# 5_EEPROM.net
KiCad netlist of a schematic drawn in Altium Designer
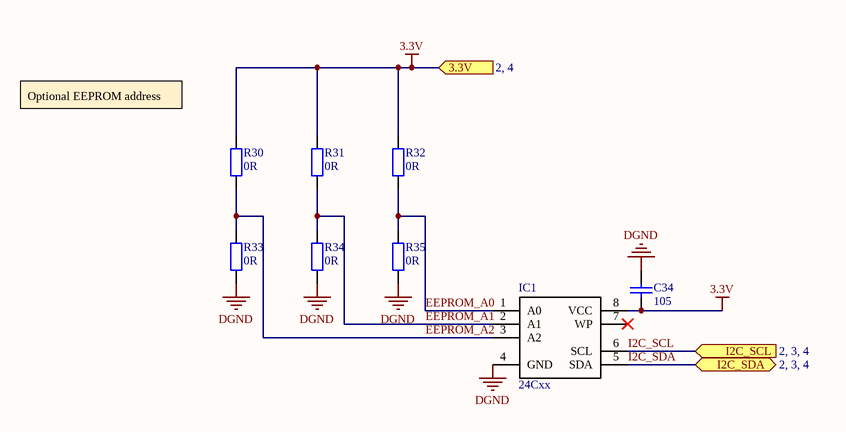
[diagram p0: [5]EEPROM.SchDoc]

(export (version "E")
  (design (tool "Eeschema 10.0.6"))
  (components
    (comp (ref "C34")
      (value "105")
      (footprint "tu 0805")
      (description "Dán")
      (libsource (lib "Tu dien") (part "Tu 0805 105 50V 10%"))
    )
    (comp (ref "IC1")
      (value "24Cxx")
      (footprint "SO8")
      (description "Standard 2-Wire Bus Interface Serial EEPROM")
      (fields (field (name "COPYRIGHT BY") "VanDungEvn"))
      (libsource (lib "LIBRARY") (part "24Cxx"))
    )
    (comp (ref "R30")
      (value "0R")
      (footprint "tro smd 0805")
      (description "Dán")
      (libsource (lib "Dien Tro") (part "Tro 0805 5% 0R"))
    )
    (comp (ref "R31")
      (value "0R")
      (footprint "tro smd 0805")
      (description "Dán")
      (libsource (lib "Dien Tro") (part "Tro 0805 5% 0R"))
    )
    (comp (ref "R32")
      (value "0R")
      (footprint "tro smd 0805")
      (description "Dán")
      (libsource (lib "Dien Tro") (part "Tro 0805 5% 0R"))
    )
    (comp (ref "R33")
      (value "0R")
      (footprint "tro smd 0805")
      (description "Dán")
      (libsource (lib "Dien Tro") (part "Tro 0805 5% 0R"))
    )
    (comp (ref "R34")
      (value "0R")
      (footprint "tro smd 0805")
      (description "Dán")
      (libsource (lib "Dien Tro") (part "Tro 0805 5% 0R"))
    )
    (comp (ref "R35")
      (value "0R")
      (footprint "tro smd 0805")
      (description "Dán")
      (libsource (lib "Dien Tro") (part "Tro 0805 5% 0R"))
    )
  )
  (nets
    (net (code "1") (name "/EEPROM_A0") (class "Default")
      (node (ref "IC1") (pin "1") (pinfunction "A0_1") (pintype "passive"))
      (node (ref "R32") (pin "1") (pinfunction "1_1") (pintype "passive"))
      (node (ref "R35") (pin "2") (pinfunction "2_2") (pintype "passive"))
    )
    (net (code "2") (name "/EEPROM_A1") (class "Default")
      (node (ref "IC1") (pin "2") (pinfunction "A1_2") (pintype "passive"))
      (node (ref "R31") (pin "1") (pinfunction "1_1") (pintype "passive"))
      (node (ref "R34") (pin "2") (pinfunction "2_2") (pintype "passive"))
    )
    (net (code "3") (name "/EEPROM_A2") (class "Default")
      (node (ref "IC1") (pin "3") (pinfunction "A2_3") (pintype "passive"))
      (node (ref "R30") (pin "1") (pinfunction "1_1") (pintype "passive"))
      (node (ref "R33") (pin "2") (pinfunction "2_2") (pintype "passive"))
    )
    (net (code "4") (name "/I2C_SCL") (class "Default")
      (node (ref "IC1") (pin "6") (pinfunction "SCL_6") (pintype "passive"))
    )
    (net (code "5") (name "/I2C_SDA") (class "Default")
      (node (ref "IC1") (pin "5") (pinfunction "SDA_5") (pintype "passive"))
    )
    (net (code "6") (name "3.3V") (class "Default")
      (node (ref "C34") (pin "2") (pinfunction "2_2") (pintype "passive"))
      (node (ref "IC1") (pin "8") (pinfunction "VCC_8") (pintype "passive"))
      (node (ref "R30") (pin "2") (pinfunction "2_2") (pintype "passive"))
      (node (ref "R31") (pin "2") (pinfunction "2_2") (pintype "passive"))
      (node (ref "R32") (pin "2") (pinfunction "2_2") (pintype "passive"))
    )
    (net (code "7") (name "DGND") (class "Default")
      (node (ref "C34") (pin "1") (pinfunction "1_1") (pintype "passive"))
      (node (ref "IC1") (pin "4") (pinfunction "GND_4") (pintype "passive"))
      (node (ref "R33") (pin "1") (pinfunction "1_1") (pintype "passive"))
      (node (ref "R34") (pin "1") (pinfunction "1_1") (pintype "passive"))
      (node (ref "R35") (pin "1") (pinfunction "1_1") (pintype "passive"))
    )
    (net (code "8") (name "unconnected-(IC1-WP-Pad7)") (class "Default")
      (node (ref "IC1") (pin "7") (pinfunction "WP_7") (pintype "passive+no_connect"))
    )
  )
)
